# Boost.net
KiCad netlist of a schematic drawn in Altium Designer
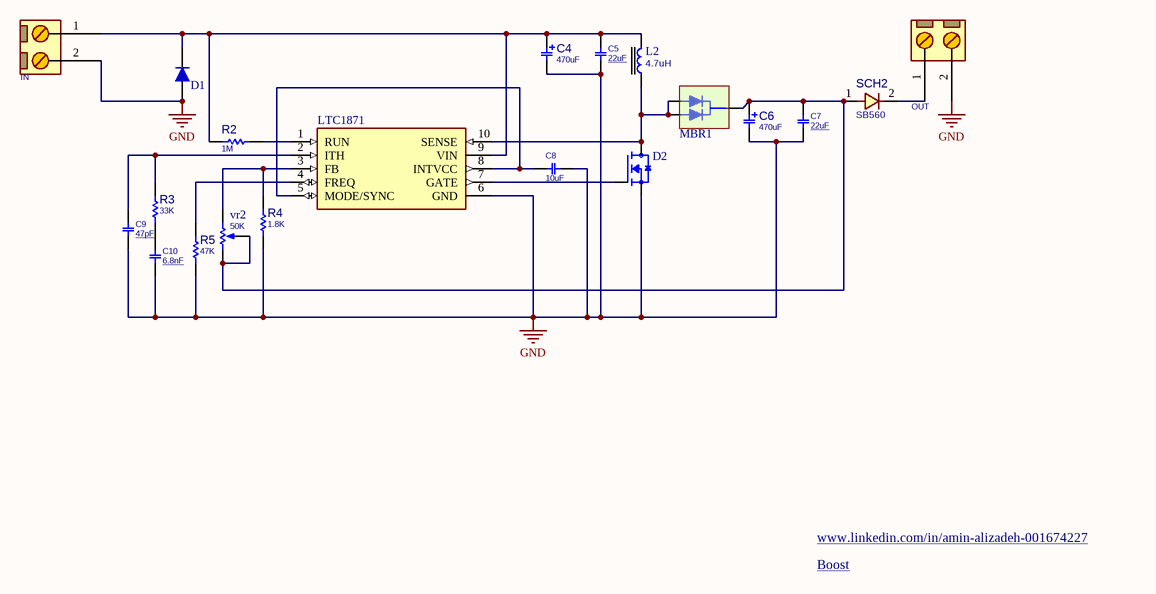
[diagram p0: Boost.SchDoc]

(export (version "E")
  (design (tool "Eeschema 10.0.6"))
  (components
    (comp (ref "C4")
      (value "470uF")
      (footprint "C_EL_10_10")
      (description "CAP, THD, ELEC,")
      (fields (field (name "MANF_P#") "MANF_PART#") (field (name "MANF") "MANF"))
      (libsource (lib "passive_smd") (part "CAP_SMD_EL"))
    )
    (comp (ref "C5")
      (value "22uF")
      (footprint "C1206")
      (description "CAP, MLCC, 1nF, 50V, C0G, 10%, 0402")
      (fields (field (name "MANF_P#") "MANF_PART#") (field (name "MANF") "Murata"))
      (libsource (lib "passive_smd") (part "CAP_SMD_MLCC"))
    )
    (comp (ref "C6")
      (value "470uF")
      (footprint "C_EL_10_10")
      (description "CAP, THD, ELEC,")
      (fields (field (name "MANF_P#") "MANF_PART#") (field (name "MANF") "MANF"))
      (libsource (lib "passive_smd") (part "CAP_SMD_EL"))
    )
    (comp (ref "C7")
      (value "22uF")
      (footprint "C1206")
      (description "CAP, MLCC, 1nF, 50V, C0G, 10%, 0402")
      (fields (field (name "MANF_P#") "MANF_PART#") (field (name "MANF") "Murata"))
      (libsource (lib "passive_smd") (part "CAP_SMD_MLCC"))
    )
    (comp (ref "C8")
      (value "10uF")
      (footprint "C0805")
      (description "CAP, MLCC, 1nF, 50V, C0G, 10%, 0402")
      (fields (field (name "MANF_P#") "MANF_PART#") (field (name "MANF") "Murata"))
      (libsource (lib "passive_smd") (part "CAP_SMD_MLCC"))
    )
    (comp (ref "C9")
      (value "47pF")
      (footprint "C0805")
      (description "CAP, MLCC, 1nF, 50V, C0G, 10%, 0402")
      (fields (field (name "MANF_P#") "MANF_PART#") (field (name "MANF") "Murata"))
      (libsource (lib "passive_smd") (part "CAP_SMD_MLCC"))
    )
    (comp (ref "C10")
      (value "6.8nF")
      (footprint "C0805")
      (description "CAP, MLCC, 1nF, 50V, C0G, 10%, 0402")
      (fields (field (name "MANF_P#") "MANF_PART#") (field (name "MANF") "Murata"))
      (libsource (lib "passive_smd") (part "CAP_SMD_MLCC"))
    )
    (comp (ref "D1")
      (value "1n4007")
      (footprint "DIOM4629X24N")
      (description "Standard Rectifiers")
      (fields (field (name "MANUFACTURER") "DC COMPONENTS") (field (name "DESIGNER") "Abbas Basereh"))
      (libsource (lib "Altium") (part "1n4007 SMD M7"))
    )
    (comp (ref "D2")
      (value "AOD4184A")
      (footprint "DPAK228P994X240-4N")
      (description "N-Channel 40 V 13A (Ta), 50A (Tc) 2.3W (Ta), 50W (Tc) Surface Mount TO-252 (DPAK)")
      (fields (field (name "MF") "Alpha & Omega Semiconductor Inc."))
      (libsource (lib "AOD4184A") (part "AOD4184A"))
    )
    (comp (ref "IN")
      (value "CONN_TB2")
      (footprint "TBG_2")
      (description "CONN, TERMINAL BLOCK, 5.08mm pitch")
      (libsource (lib "conn_power_terminalB") (part "CONN_TB2"))
    )
    (comp (ref "L2")
      (value "4.7uH")
      (footprint "L_7")
      (description "INDUCTOR, POWER, SMD")
      (libsource (lib "inductor_power") (part "INDPWR_SMD"))
    )
    (comp (ref "LTC1871")
      (value "LTC1871HMS#PBF")
      (footprint "SamacSys:SOP50P490X110-10N")
      (description "Integrated Circuit")
      (fields (field (name "MOUSER PART NUMBER") "584-LTC1871HMS#PBF"))
      (libsource (lib "SamacSys") (part "LTC1871HMS#PBF"))
    )
    (comp (ref "MBR1")
      (value "MBR20100CT")
      (footprint "TO220")
      (description "SCHOTTKY BARRIER 20 AMPERES 80−100 VOLTS")
      (libsource (lib "Sajad_Altium_Library") (part "MBR20100CT"))
    )
    (comp (ref "OUT")
      (value "CONN_TB2")
      (footprint "TBG_2")
      (description "CONN, TERMINAL BLOCK, 5.08mm pitch")
      (libsource (lib "") (part "CONN_TB2_1"))
    )
    (comp (ref "R2")
      (value "1M")
      (footprint "R0805")
      (description "RESISTOR, SMD")
      (libsource (lib "passive_smd") (part "RES_SMD_0805"))
    )
    (comp (ref "R3")
      (value "33K")
      (footprint "R0805")
      (description "RESISTOR, SMD")
      (libsource (lib "passive_smd") (part "RES_SMD_0805"))
    )
    (comp (ref "R4")
      (value "1.8K")
      (footprint "R0805")
      (description "RESISTOR, SMD")
      (libsource (lib "passive_smd") (part "RES_SMD_0805"))
    )
    (comp (ref "R5")
      (value "47K")
      (footprint "R0805")
      (description "RESISTOR, SMD")
      (libsource (lib "passive_smd") (part "RES_SMD_0805"))
    )
    (comp (ref "SCH2")
      (value "SB560")
      (footprint "D_AX07_DO27")
      (description "DIODE, THD")
      (fields (field (name "MANF") "MANF") (field (name "MANF_P#") "1N4001"))
      (libsource (lib "diode") (part "DIODE_THD"))
    )
    (comp (ref "vr2")
      (value "50K")
      (footprint "POT_3296W")
      (description "RESISTOR, THD, Potentiometer Multiturn, most Popular")
      (libsource (lib "resistor_pot_trimmer") (part "RES_THD_POT_MULTITURN"))
    )
  )
  (nets
    (net (code "1") (name "GND") (class "Default")
      (node (ref "C10") (pin "2") (pinfunction "2_2") (pintype "passive"))
      (node (ref "C4") (pin "2") (pinfunction "2_2") (pintype "passive"))
      (node (ref "C5") (pin "1") (pinfunction "1_1") (pintype "passive"))
      (node (ref "C6") (pin "2") (pinfunction "2_2") (pintype "passive"))
      (node (ref "C7") (pin "1") (pinfunction "1_1") (pintype "passive"))
      (node (ref "C8") (pin "2") (pinfunction "2_2") (pintype "passive"))
      (node (ref "C9") (pin "2") (pinfunction "2_2") (pintype "passive"))
      (node (ref "D1") (pin "1") (pintype "passive"))
      (node (ref "D2") (pin "3") (pinfunction "S_3") (pintype "passive"))
      (node (ref "IN") (pin "2") (pinfunction "2_2") (pintype "passive"))
      (node (ref "LTC1871") (pin "6") (pinfunction "GND_6") (pintype "power_in"))
      (node (ref "OUT") (pin "2") (pinfunction "2_2") (pintype "passive"))
      (node (ref "R4") (pin "2") (pinfunction "2_2") (pintype "passive"))
      (node (ref "R5") (pin "2") (pinfunction "2_2") (pintype "passive"))
    )
    (net (code "2") (name "Net-(C10-Pad1)") (class "Default")
      (node (ref "C10") (pin "1") (pinfunction "1_1") (pintype "passive"))
      (node (ref "R3") (pin "2") (pinfunction "2_2") (pintype "passive"))
    )
    (net (code "3") (name "Net-(D2-D)") (class "Default")
      (node (ref "D2") (pin "4") (pinfunction "D_4") (pintype "passive"))
      (node (ref "L2") (pin "1") (pinfunction "1_1") (pintype "passive"))
      (node (ref "LTC1871") (pin "10") (pinfunction "SENSE_10") (pintype "input"))
      (node (ref "MBR1") (pin "1") (pinfunction "A1_1") (pintype "passive"))
      (node (ref "MBR1") (pin "3") (pinfunction "A2_3") (pintype "passive"))
    )
    (net (code "4") (name "Net-(D2-G)") (class "Default")
      (node (ref "D2") (pin "1") (pinfunction "G_1") (pintype "passive"))
      (node (ref "LTC1871") (pin "7") (pinfunction "GATE_7") (pintype "output"))
    )
    (net (code "5") (name "Net-(LTC1871-FB)") (class "Default")
      (node (ref "LTC1871") (pin "3") (pinfunction "FB_3") (pintype "input"))
      (node (ref "R4") (pin "1") (pinfunction "1_1") (pintype "passive"))
      (node (ref "vr2") (pin "3") (pinfunction "BOT_3") (pintype "passive"))
    )
    (net (code "6") (name "Net-(LTC1871-FREQ)") (class "Default")
      (node (ref "LTC1871") (pin "4") (pinfunction "FREQ_4") (pintype "bidirectional"))
      (node (ref "R5") (pin "1") (pinfunction "1_1") (pintype "passive"))
    )
    (net (code "7") (name "Net-(LTC1871-INTVCC)") (class "Default")
      (node (ref "C8") (pin "1") (pinfunction "1_1") (pintype "passive"))
      (node (ref "LTC1871") (pin "5") (pinfunction "MODE/SYNC_5") (pintype "bidirectional"))
      (node (ref "LTC1871") (pin "8") (pinfunction "INTVCC_8") (pintype "output"))
    )
    (net (code "8") (name "Net-(LTC1871-ITH)") (class "Default")
      (node (ref "C9") (pin "1") (pinfunction "1_1") (pintype "passive"))
      (node (ref "LTC1871") (pin "2") (pinfunction "ITH_2") (pintype "input"))
      (node (ref "R3") (pin "1") (pinfunction "1_1") (pintype "passive"))
    )
    (net (code "9") (name "Net-(LTC1871-RUN)") (class "Default")
      (node (ref "LTC1871") (pin "1") (pinfunction "RUN_1") (pintype "input"))
      (node (ref "R2") (pin "1") (pinfunction "1_1") (pintype "passive"))
    )
    (net (code "10") (name "Net-(LTC1871-VIN)") (class "Default")
      (node (ref "C4") (pin "1") (pinfunction "1_1") (pintype "passive"))
      (node (ref "C5") (pin "2") (pinfunction "2_2") (pintype "passive"))
      (node (ref "D1") (pin "2") (pintype "passive"))
      (node (ref "IN") (pin "1") (pinfunction "1_1") (pintype "passive"))
      (node (ref "L2") (pin "2") (pinfunction "2_2") (pintype "passive"))
      (node (ref "LTC1871") (pin "9") (pinfunction "VIN_9") (pintype "power_in"))
      (node (ref "R2") (pin "2") (pinfunction "2_2") (pintype "passive"))
    )
    (net (code "11") (name "Net-(MBR1-K)") (class "Default")
      (node (ref "C6") (pin "1") (pinfunction "1_1") (pintype "passive"))
      (node (ref "C7") (pin "2") (pinfunction "2_2") (pintype "passive"))
      (node (ref "MBR1") (pin "2") (pinfunction "K_2") (pintype "passive"))
      (node (ref "SCH2") (pin "1") (pinfunction "1_1") (pintype "passive"))
      (node (ref "vr2") (pin "1") (pinfunction "TOP_1") (pintype "passive"))
      (node (ref "vr2") (pin "2") (pinfunction "TAP_2") (pintype "passive"))
    )
    (net (code "12") (name "Net-(OUT-Pad1)") (class "Default")
      (node (ref "OUT") (pin "1") (pinfunction "1_1") (pintype "passive"))
      (node (ref "SCH2") (pin "2") (pinfunction "2_2") (pintype "passive"))
    )
  )
)
